# HC-06_Arduino_UNO_Adapter.net
KiCad netlist of a schematic drawn in EAGLE
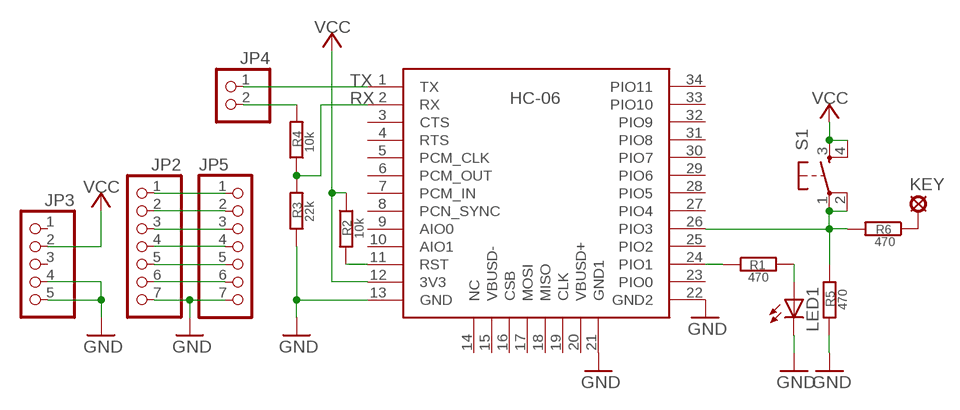
[diagram p0: schematic, sheet 1]

(export (version "E")
  (design (tool "Eeschema 10.0.6"))
  (components
    (comp (ref "HC-06")
      (value "HC_05")
      (footprint "eagle-import:BLUETOOTH_SMD")
      (libsource (lib "eagle-import") (part "HC_05"))
    )
    (comp (ref "JP2")
      (value "PINHD-1X7")
      (footprint "eagle-import:1X07")
      (libsource (lib "eagle-import") (part "PINHD-1X7"))
    )
    (comp (ref "JP3")
      (value "PINHD-1X5")
      (footprint "eagle-import:1X05")
      (libsource (lib "eagle-import") (part "PINHD-1X5"))
    )
    (comp (ref "JP4")
      (value "PINHD-1X2")
      (footprint "eagle-import:1X02")
      (libsource (lib "eagle-import") (part "PINHD-1X2"))
    )
    (comp (ref "JP5")
      (value "PINHD-1X7")
      (footprint "eagle-import:1X07")
      (libsource (lib "eagle-import") (part "PINHD-1X7"))
    )
    (comp (ref "KEY")
      (value "LSP10")
      (footprint "eagle-import:LSP10")
      (libsource (lib "eagle-import") (part "LSP10"))
    )
    (comp (ref "LED1")
      (value "LED3MM")
      (footprint "eagle-import:LED3MM")
      (libsource (lib "eagle-import") (part "LED3MM"))
    )
    (comp (ref "R1")
      (value "470")
      (footprint "eagle-import:0204_5")
      (libsource (lib "eagle-import") (part "R-EU_0204/5"))
    )
    (comp (ref "R2")
      (value "10k")
      (footprint "eagle-import:0204_5")
      (libsource (lib "eagle-import") (part "R-EU_0204/5"))
    )
    (comp (ref "R3")
      (value "22k")
      (footprint "eagle-import:0204_5")
      (libsource (lib "eagle-import") (part "R-EU_0204/5"))
    )
    (comp (ref "R4")
      (value "10k")
      (footprint "eagle-import:0204_5")
      (libsource (lib "eagle-import") (part "R-EU_0204/5"))
    )
    (comp (ref "R5")
      (value "470")
      (footprint "eagle-import:0204_5")
      (libsource (lib "eagle-import") (part "R-EU_0204/5"))
    )
    (comp (ref "R6")
      (value "470")
      (footprint "eagle-import:0204_5")
      (libsource (lib "eagle-import") (part "R-EU_0204/5"))
    )
    (comp (ref "S1")
      (value "TACTILE-SWITCH-PTH")
      (footprint "eagle-import:TAC-SWITCH-PTH")
      (libsource (lib "eagle-import") (part "TACTILE-SWITCH-PTH"))
    )
  )
  (nets
    (net (code "1") (name "/RX") (class "Default")
      (node (ref "HC-06") (pin "2") (pinfunction "RX_2") (pintype "bidirectional"))
      (node (ref "R3") (pin "2") (pinfunction "2_2") (pintype "passive"))
      (node (ref "R4") (pin "1") (pinfunction "1_1") (pintype "passive"))
    )
    (net (code "2") (name "/TX") (class "Default")
      (node (ref "HC-06") (pin "1") (pinfunction "TX_1") (pintype "bidirectional"))
      (node (ref "JP4") (pin "1") (pinfunction "1_1") (pintype "passive"))
    )
    (net (code "3") (name "GND") (class "Default")
      (node (ref "HC-06") (pin "13") (pinfunction "GND_13") (pintype "bidirectional"))
      (node (ref "HC-06") (pin "21") (pinfunction "GND1_21") (pintype "bidirectional"))
      (node (ref "HC-06") (pin "22") (pinfunction "GND2_22") (pintype "bidirectional"))
      (node (ref "JP2") (pin "7") (pinfunction "7_7") (pintype "passive"))
      (node (ref "JP3") (pin "4") (pinfunction "4_4") (pintype "passive"))
      (node (ref "JP3") (pin "5") (pinfunction "5_5") (pintype "passive"))
      (node (ref "JP5") (pin "7") (pinfunction "7_7") (pintype "passive"))
      (node (ref "LED1") (pin "K") (pinfunction "C_K") (pintype "passive"))
      (node (ref "R3") (pin "1") (pinfunction "1_1") (pintype "passive"))
      (node (ref "R5") (pin "2") (pinfunction "2_2") (pintype "passive"))
    )
    (net (code "4") (name "Net-(HC-06-PIO1)") (class "Default")
      (node (ref "HC-06") (pin "24") (pinfunction "PIO1_24") (pintype "bidirectional"))
      (node (ref "R1") (pin "1") (pinfunction "1_1") (pintype "passive"))
    )
    (net (code "5") (name "Net-(HC-06-PIO3)") (class "Default")
      (node (ref "HC-06") (pin "26") (pinfunction "PIO3_26") (pintype "bidirectional"))
      (node (ref "R5") (pin "1") (pinfunction "1_1") (pintype "passive"))
      (node (ref "R6") (pin "2") (pinfunction "2_2") (pintype "passive"))
      (node (ref "S1") (pin "1") (pinfunction "1_1") (pintype "passive"))
      (node (ref "S1") (pin "2") (pinfunction "2_2") (pintype "passive"))
    )
    (net (code "6") (name "Net-(HC-06-RST)") (class "Default")
      (node (ref "HC-06") (pin "11") (pinfunction "RST_11") (pintype "bidirectional"))
      (node (ref "R2") (pin "2") (pinfunction "2_2") (pintype "passive"))
    )
    (net (code "7") (name "Net-(JP2-Pad1)") (class "Default")
      (node (ref "JP2") (pin "1") (pinfunction "1_1") (pintype "passive"))
      (node (ref "JP5") (pin "1") (pinfunction "1_1") (pintype "passive"))
    )
    (net (code "8") (name "Net-(JP2-Pad2)") (class "Default")
      (node (ref "JP2") (pin "2") (pinfunction "2_2") (pintype "passive"))
      (node (ref "JP5") (pin "2") (pinfunction "2_2") (pintype "passive"))
    )
    (net (code "9") (name "Net-(JP2-Pad3)") (class "Default")
      (node (ref "JP2") (pin "3") (pinfunction "3_3") (pintype "passive"))
      (node (ref "JP5") (pin "3") (pinfunction "3_3") (pintype "passive"))
    )
    (net (code "10") (name "Net-(JP2-Pad4)") (class "Default")
      (node (ref "JP2") (pin "4") (pinfunction "4_4") (pintype "passive"))
      (node (ref "JP5") (pin "4") (pinfunction "4_4") (pintype "passive"))
    )
    (net (code "11") (name "Net-(JP2-Pad5)") (class "Default")
      (node (ref "JP2") (pin "5") (pinfunction "5_5") (pintype "passive"))
      (node (ref "JP5") (pin "5") (pinfunction "5_5") (pintype "passive"))
    )
    (net (code "12") (name "Net-(JP2-Pad6)") (class "Default")
      (node (ref "JP2") (pin "6") (pinfunction "6_6") (pintype "passive"))
      (node (ref "JP5") (pin "6") (pinfunction "6_6") (pintype "passive"))
    )
    (net (code "13") (name "Net-(JP4-Pad2)") (class "Default")
      (node (ref "JP4") (pin "2") (pinfunction "2_2") (pintype "passive"))
      (node (ref "R4") (pin "2") (pinfunction "2_2") (pintype "passive"))
    )
    (net (code "14") (name "Net-(KEY-PadMP)") (class "Default")
      (node (ref "KEY") (pin "MP") (pinfunction "MP_MP") (pintype "passive"))
      (node (ref "R6") (pin "1") (pinfunction "1_1") (pintype "passive"))
    )
    (net (code "15") (name "Net-(LED1-PadA)") (class "Default")
      (node (ref "LED1") (pin "A") (pinfunction "A_A") (pintype "passive"))
      (node (ref "R1") (pin "2") (pinfunction "2_2") (pintype "passive"))
    )
    (net (code "16") (name "VCC") (class "Default")
      (node (ref "HC-06") (pin "12") (pinfunction "3V3_12") (pintype "bidirectional"))
      (node (ref "JP3") (pin "2") (pinfunction "2_2") (pintype "passive"))
      (node (ref "R2") (pin "1") (pinfunction "1_1") (pintype "passive"))
      (node (ref "S1") (pin "3") (pinfunction "3_3") (pintype "passive"))
      (node (ref "S1") (pin "4") (pinfunction "4_4") (pintype "passive"))
    )
    (net (code "17") (name "unconnected-(HC-06-AIO0-Pad9)") (class "Default")
      (node (ref "HC-06") (pin "9") (pinfunction "AIO0_9") (pintype "bidirectional"))
    )
    (net (code "18") (name "unconnected-(HC-06-AIO1-Pad10)") (class "Default")
      (node (ref "HC-06") (pin "10") (pinfunction "AIO1_10") (pintype "bidirectional"))
    )
    (net (code "19") (name "unconnected-(HC-06-CLK-Pad19)") (class "Default")
      (node (ref "HC-06") (pin "19") (pinfunction "CLK_19") (pintype "bidirectional"))
    )
    (net (code "20") (name "unconnected-(HC-06-CSB-Pad16)") (class "Default")
      (node (ref "HC-06") (pin "16") (pinfunction "CSB_16") (pintype "bidirectional"))
    )
    (net (code "21") (name "unconnected-(HC-06-CTS-Pad3)") (class "Default")
      (node (ref "HC-06") (pin "3") (pinfunction "CTS_3") (pintype "bidirectional"))
    )
    (net (code "22") (name "unconnected-(HC-06-MISO-Pad18)") (class "Default")
      (node (ref "HC-06") (pin "18") (pinfunction "MISO_18") (pintype "bidirectional"))
    )
    (net (code "23") (name "unconnected-(HC-06-MOSI-Pad17)") (class "Default")
      (node (ref "HC-06") (pin "17") (pinfunction "MOSI_17") (pintype "bidirectional"))
    )
    (net (code "24") (name "unconnected-(HC-06-NC-Pad14)") (class "Default")
      (node (ref "HC-06") (pin "14") (pinfunction "NC_14") (pintype "bidirectional"))
    )
    (net (code "25") (name "unconnected-(HC-06-PCM_CLK-Pad5)") (class "Default")
      (node (ref "HC-06") (pin "5") (pinfunction "PCM_CLK_5") (pintype "bidirectional"))
    )
    (net (code "26") (name "unconnected-(HC-06-PCM_IN-Pad7)") (class "Default")
      (node (ref "HC-06") (pin "7") (pinfunction "PCM_IN_7") (pintype "bidirectional"))
    )
    (net (code "27") (name "unconnected-(HC-06-PCM_OUT-Pad6)") (class "Default")
      (node (ref "HC-06") (pin "6") (pinfunction "PCM_OUT_6") (pintype "bidirectional"))
    )
    (net (code "28") (name "unconnected-(HC-06-PCN_SYNC-Pad8)") (class "Default")
      (node (ref "HC-06") (pin "8") (pinfunction "PCN_SYNC_8") (pintype "bidirectional"))
    )
    (net (code "29") (name "unconnected-(HC-06-PIO0-Pad23)") (class "Default")
      (node (ref "HC-06") (pin "23") (pinfunction "PIO0_23") (pintype "bidirectional"))
    )
    (net (code "30") (name "unconnected-(HC-06-PIO2-Pad25)") (class "Default")
      (node (ref "HC-06") (pin "25") (pinfunction "PIO2_25") (pintype "bidirectional"))
    )
    (net (code "31") (name "unconnected-(HC-06-PIO4-Pad27)") (class "Default")
      (node (ref "HC-06") (pin "27") (pinfunction "PIO4_27") (pintype "bidirectional"))
    )
    (net (code "32") (name "unconnected-(HC-06-PIO5-Pad28)") (class "Default")
      (node (ref "HC-06") (pin "28") (pinfunction "PIO5_28") (pintype "bidirectional"))
    )
    (net (code "33") (name "unconnected-(HC-06-PIO6-Pad29)") (class "Default")
      (node (ref "HC-06") (pin "29") (pinfunction "PIO6_29") (pintype "bidirectional"))
    )
    (net (code "34") (name "unconnected-(HC-06-PIO7-Pad30)") (class "Default")
      (node (ref "HC-06") (pin "30") (pinfunction "PIO7_30") (pintype "bidirectional"))
    )
    (net (code "35") (name "unconnected-(HC-06-PIO8-Pad31)") (class "Default")
      (node (ref "HC-06") (pin "31") (pinfunction "PIO8_31") (pintype "bidirectional"))
    )
    (net (code "36") (name "unconnected-(HC-06-PIO9-Pad32)") (class "Default")
      (node (ref "HC-06") (pin "32") (pinfunction "PIO9_32") (pintype "bidirectional"))
    )
    (net (code "37") (name "unconnected-(HC-06-PIO10-Pad33)") (class "Default")
      (node (ref "HC-06") (pin "33") (pinfunction "PIO10_33") (pintype "bidirectional"))
    )
    (net (code "38") (name "unconnected-(HC-06-PIO11-Pad34)") (class "Default")
      (node (ref "HC-06") (pin "34") (pinfunction "PIO11_34") (pintype "bidirectional"))
    )
    (net (code "39") (name "unconnected-(HC-06-RTS-Pad4)") (class "Default")
      (node (ref "HC-06") (pin "4") (pinfunction "RTS_4") (pintype "bidirectional"))
    )
    (net (code "40") (name "unconnected-(HC-06-VBUSD+-Pad20)") (class "Default")
      (node (ref "HC-06") (pin "20") (pinfunction "VBUSD+_20") (pintype "bidirectional"))
    )
    (net (code "41") (name "unconnected-(HC-06-VBUSD--Pad15)") (class "Default")
      (node (ref "HC-06") (pin "15") (pinfunction "VBUSD-_15") (pintype "bidirectional"))
    )
    (net (code "42") (name "unconnected-(JP3-Pad1)") (class "Default")
      (node (ref "JP3") (pin "1") (pinfunction "1_1") (pintype "passive"))
    )
    (net (code "43") (name "unconnected-(JP3-Pad3)") (class "Default")
      (node (ref "JP3") (pin "3") (pinfunction "3_3") (pintype "passive"))
    )
  )
)
